# chipheater_01.net
KiCad netlist of a schematic drawn in EAGLE
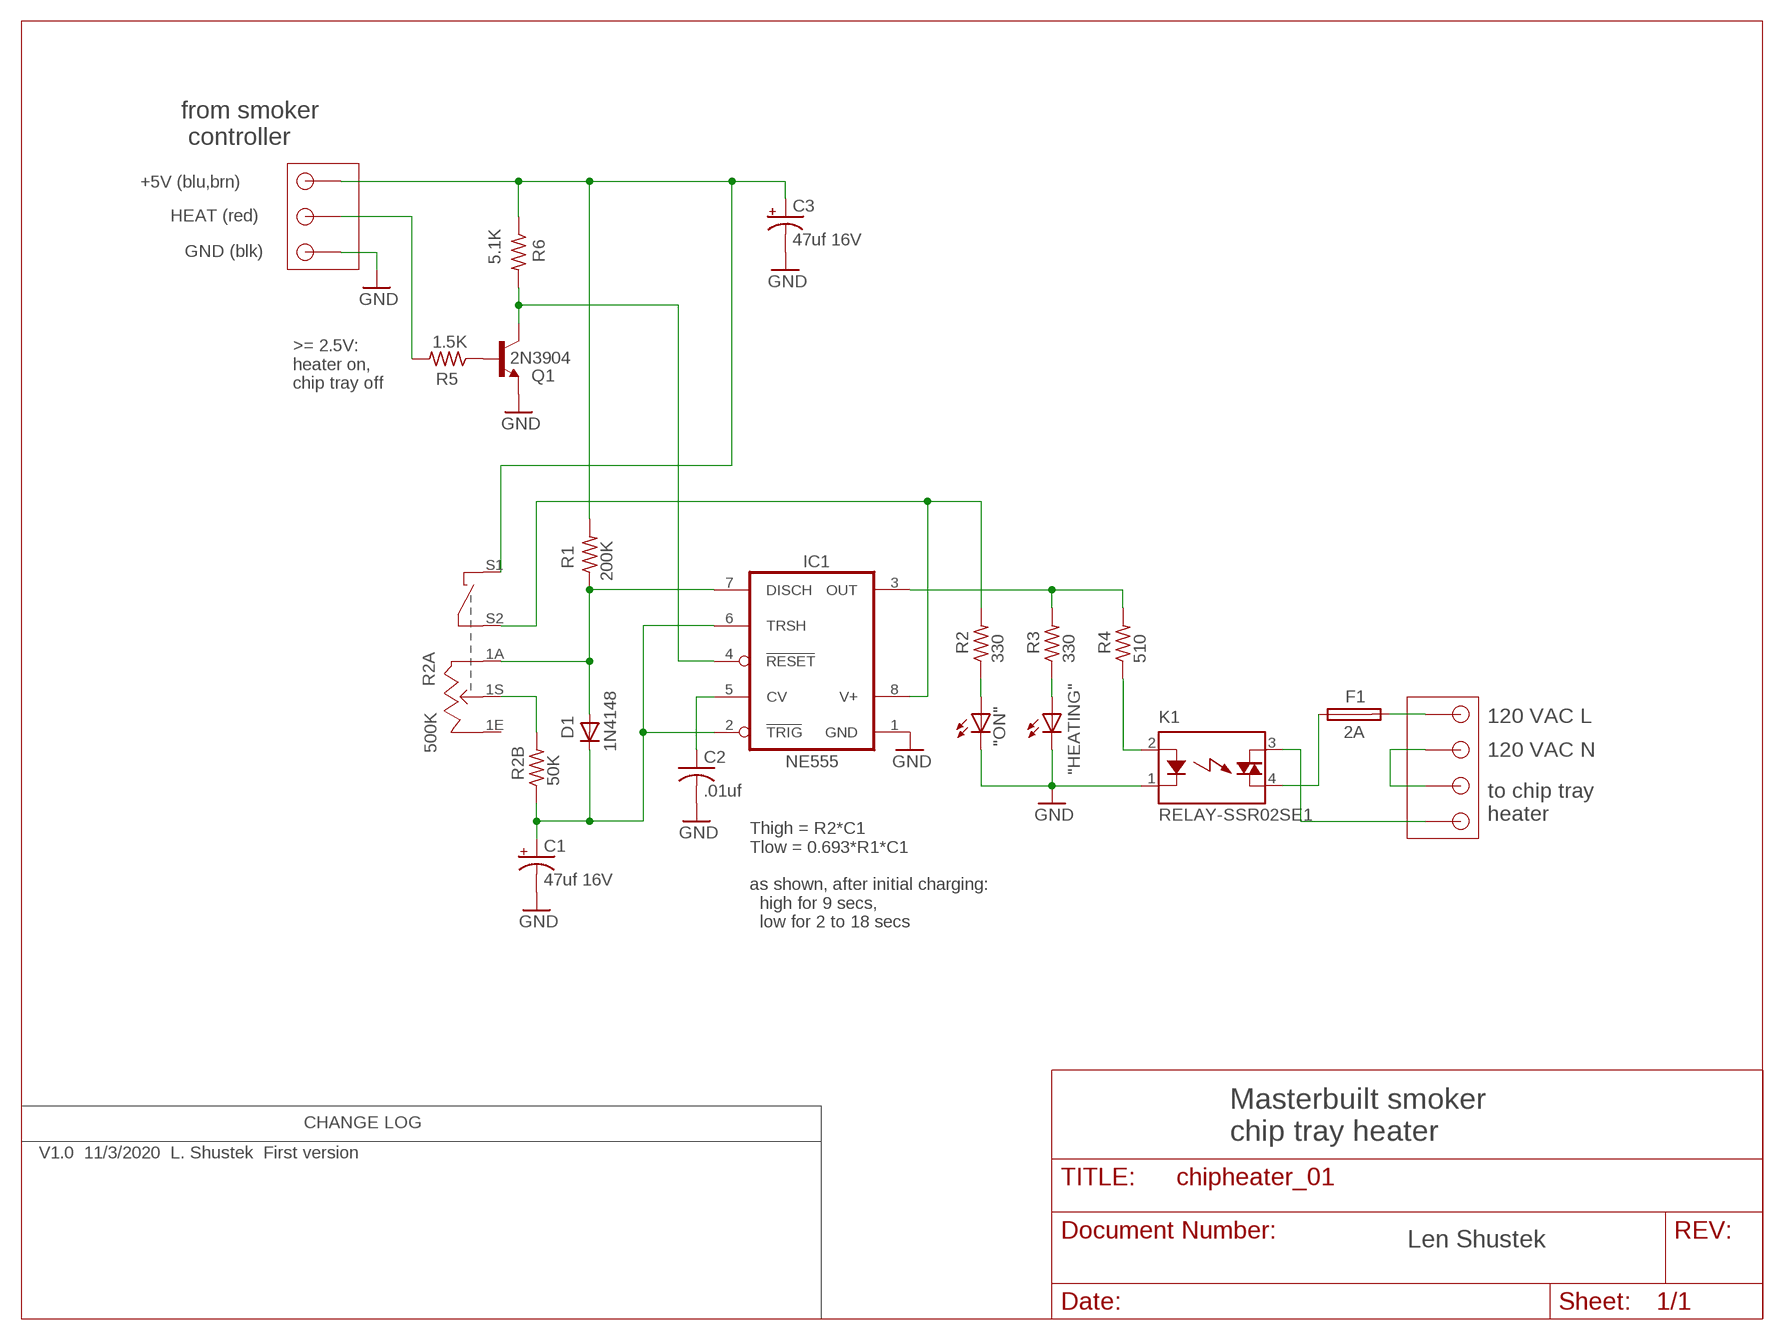
[diagram p0: schematic, sheet 1]

(export (version "E")
  (design (tool "Eeschema 10.0.6"))
  (components
    (comp (ref "\"HEATING\"")
      (value "LED5MM")
      (footprint "eagle-import:LED5MM")
      (libsource (lib "eagle-import") (part "LED5MM"))
    )
    (comp (ref "\"ON\"")
      (value "LED5MM")
      (footprint "eagle-import:LED5MM")
      (libsource (lib "eagle-import") (part "LED5MM"))
    )
    (comp (ref "C1")
      (value "47uf 16V")
      (footprint "eagle-import:E2,5-5")
      (libsource (lib "eagle-import") (part "CPOL-USE2.5-5"))
    )
    (comp (ref "C2")
      (value ".01uf")
      (footprint "eagle-import:C025-025X050")
      (libsource (lib "eagle-import") (part "C-US025-025X050"))
    )
    (comp (ref "C3")
      (value "47uf 16V")
      (footprint "eagle-import:E2,5-5")
      (libsource (lib "eagle-import") (part "CPOL-USE2.5-5"))
    )
    (comp (ref "D1")
      (value "1N4148")
      (footprint "eagle-import:DO-1N4148")
      (libsource (lib "eagle-import") (part "DIODEDO-1N4148"))
    )
    (comp (ref "F1")
      (value "2A")
      (footprint "eagle-import:SH22,5A")
      (libsource (lib "eagle-import") (part "FUSESH22,5A"))
    )
    (comp (ref "IC1")
      (value "NE555")
      (footprint "eagle-import:DIL08")
      (fields (field (name "MF") "MAXIM") (field (name "MPN") "ICM7555IPA+"))
      (libsource (lib "eagle-import") (part "ICM7555"))
    )
    (comp (ref "K1")
      (value "RELAY-SSR02SE1")
      (footprint "eagle-import:RELAY-SSR")
      (libsource (lib "eagle-import") (part "RELAY-SSR02SE1"))
    )
    (comp (ref "Q1")
      (value "2N3904")
      (footprint "eagle-import:TO92")
      (libsource (lib "eagle-import") (part "2N3904"))
    )
    (comp (ref "R1")
      (value "200K")
      (footprint "eagle-import:0204_7")
      (libsource (lib "eagle-import") (part "R-US_0204/7"))
    )
    (comp (ref "R2")
      (value "330")
      (footprint "eagle-import:0204_7")
      (libsource (lib "eagle-import") (part "R-US_0204/7"))
    )
    (comp (ref "R2A")
      (value "500K")
      (footprint "eagle-import:POT_W_SWITCH-UXCELL")
      (libsource (lib "eagle-import") (part "POT_W/SWITCHUXCELL"))
    )
    (comp (ref "R2B")
      (value "50K")
      (footprint "eagle-import:0204_7")
      (libsource (lib "eagle-import") (part "R-US_0204/7"))
    )
    (comp (ref "R3")
      (value "330")
      (footprint "eagle-import:0204_7")
      (libsource (lib "eagle-import") (part "R-US_0204/7"))
    )
    (comp (ref "R4")
      (value "510")
      (footprint "eagle-import:0204_7")
      (libsource (lib "eagle-import") (part "R-US_0204/7"))
    )
    (comp (ref "R5")
      (value "1.5K")
      (footprint "eagle-import:0204_7")
      (libsource (lib "eagle-import") (part "R-US_0204/7"))
    )
    (comp (ref "R6")
      (value "5.1K")
      (footprint "eagle-import:0204_7")
      (libsource (lib "eagle-import") (part "R-US_0204/7"))
    )
    (comp (ref "U$1")
      (value "CONNECTOR-4PIN")
      (footprint "eagle-import:CONNECTOR-4PIN-5MM_THIN")
      (libsource (lib "eagle-import") (part "CONNECTOR-4PIN"))
    )
    (comp (ref "U$2")
      (value "CONNECTOR-3PIN")
      (footprint "eagle-import:CONNECTOR-3PIN-5MM_THIN")
      (libsource (lib "eagle-import") (part "CONNECTOR-3PIN"))
    )
  )
  (nets
    (net (code "1") (name "GND") (class "Default")
      (node (ref "\"HEATING\"") (pin "K") (pinfunction "C_K") (pintype "passive"))
      (node (ref "\"ON\"") (pin "K") (pinfunction "C_K") (pintype "passive"))
      (node (ref "C1") (pin "-") (pinfunction "-_-") (pintype "passive"))
      (node (ref "C2") (pin "2") (pinfunction "2_2") (pintype "passive"))
      (node (ref "C3") (pin "-") (pinfunction "-_-") (pintype "passive"))
      (node (ref "IC1") (pin "1") (pinfunction "GND_1") (pintype "power_in"))
      (node (ref "K1") (pin "1") (pinfunction "K_1") (pintype "passive"))
      (node (ref "Q1") (pin "3") (pinfunction "E_3") (pintype "passive"))
      (node (ref "U$2") (pin "P$1") (pinfunction "P$1_P$1") (pintype "bidirectional"))
    )
    (net (code "2") (name "Net-(\"HEATING\"-PadA)") (class "Default")
      (node (ref "\"HEATING\"") (pin "A") (pinfunction "A_A") (pintype "passive"))
      (node (ref "R3") (pin "1") (pinfunction "1_1") (pintype "passive"))
    )
    (net (code "3") (name "Net-(\"ON\"-PadA)") (class "Default")
      (node (ref "\"ON\"") (pin "A") (pinfunction "A_A") (pintype "passive"))
      (node (ref "R2") (pin "1") (pinfunction "1_1") (pintype "passive"))
    )
    (net (code "4") (name "Net-(C3-Pad+)") (class "Default")
      (node (ref "C3") (pin "+") (pinfunction "+_+") (pintype "passive"))
      (node (ref "R1") (pin "2") (pinfunction "2_2") (pintype "passive"))
      (node (ref "R2A") (pin "S1") (pinfunction "S1_S1") (pintype "passive"))
      (node (ref "R6") (pin "1") (pinfunction "1_1") (pintype "passive"))
      (node (ref "U$2") (pin "P$3") (pinfunction "P$3_P$3") (pintype "bidirectional"))
    )
    (net (code "5") (name "Net-(F1-Pad2)") (class "Default")
      (node (ref "F1") (pin "2") (pinfunction "2_2") (pintype "passive"))
      (node (ref "U$1") (pin "P$1") (pinfunction "P$1_P$1") (pintype "bidirectional"))
    )
    (net (code "6") (name "Net-(IC1-CV)") (class "Default")
      (node (ref "C2") (pin "1") (pinfunction "1_1") (pintype "passive"))
      (node (ref "IC1") (pin "5") (pinfunction "CV_5") (pintype "passive"))
    )
    (net (code "7") (name "Net-(IC1-DISCH)") (class "Default")
      (node (ref "D1") (pin "A") (pinfunction "A_A") (pintype "passive"))
      (node (ref "IC1") (pin "7") (pinfunction "DISCH_7") (pintype "input"))
      (node (ref "R1") (pin "1") (pinfunction "1_1") (pintype "passive"))
      (node (ref "R2A") (pin "1A") (pinfunction "1A_1A") (pintype "passive"))
    )
    (net (code "8") (name "Net-(IC1-OUT)") (class "Default")
      (node (ref "IC1") (pin "3") (pinfunction "OUT_3") (pintype "output"))
      (node (ref "R3") (pin "2") (pinfunction "2_2") (pintype "passive"))
      (node (ref "R4") (pin "2") (pinfunction "2_2") (pintype "passive"))
    )
    (net (code "9") (name "Net-(IC1-RESET)") (class "Default")
      (node (ref "IC1") (pin "4") (pinfunction "RESET_4") (pintype "input"))
      (node (ref "Q1") (pin "1") (pinfunction "C_1") (pintype "passive"))
      (node (ref "R6") (pin "2") (pinfunction "2_2") (pintype "passive"))
    )
    (net (code "10") (name "Net-(IC1-TRIG)") (class "Default")
      (node (ref "C1") (pin "+") (pinfunction "+_+") (pintype "passive"))
      (node (ref "D1") (pin "C") (pinfunction "C_C") (pintype "passive"))
      (node (ref "IC1") (pin "2") (pinfunction "TRIG_2") (pintype "bidirectional"))
      (node (ref "IC1") (pin "6") (pinfunction "TRSH_6") (pintype "input"))
      (node (ref "R2B") (pin "1") (pinfunction "1_1") (pintype "passive"))
    )
    (net (code "11") (name "Net-(IC1-V+)") (class "Default")
      (node (ref "IC1") (pin "8") (pinfunction "V+_8") (pintype "power_in"))
      (node (ref "R2") (pin "2") (pinfunction "2_2") (pintype "passive"))
      (node (ref "R2A") (pin "S2") (pinfunction "S2_S2") (pintype "passive"))
    )
    (net (code "12") (name "Net-(K1-A)") (class "Default")
      (node (ref "K1") (pin "2") (pinfunction "A_2") (pintype "passive"))
      (node (ref "R4") (pin "1") (pinfunction "1_1") (pintype "passive"))
    )
    (net (code "13") (name "Net-(K1-DS1)") (class "Default")
      (node (ref "K1") (pin "3") (pinfunction "DS1_3") (pintype "passive"))
      (node (ref "U$1") (pin "P$4") (pinfunction "P$4_P$4") (pintype "bidirectional"))
    )
    (net (code "14") (name "Net-(K1-DS2)") (class "Default")
      (node (ref "F1") (pin "1") (pinfunction "1_1") (pintype "passive"))
      (node (ref "K1") (pin "4") (pinfunction "DS2_4") (pintype "passive"))
    )
    (net (code "15") (name "Net-(Q1-B)") (class "Default")
      (node (ref "Q1") (pin "2") (pinfunction "B_2") (pintype "passive"))
      (node (ref "R5") (pin "1") (pinfunction "1_1") (pintype "passive"))
    )
    (net (code "16") (name "Net-(R2A-Pad1S)") (class "Default")
      (node (ref "R2A") (pin "1S") (pinfunction "1S_1S") (pintype "passive"))
      (node (ref "R2B") (pin "2") (pinfunction "2_2") (pintype "passive"))
    )
    (net (code "17") (name "Net-(R5-Pad2)") (class "Default")
      (node (ref "R5") (pin "2") (pinfunction "2_2") (pintype "passive"))
      (node (ref "U$2") (pin "P$2") (pinfunction "P$2_P$2") (pintype "bidirectional"))
    )
    (net (code "18") (name "Net-(U$1-PadP$2)") (class "Default")
      (node (ref "U$1") (pin "P$2") (pinfunction "P$2_P$2") (pintype "bidirectional"))
      (node (ref "U$1") (pin "P$3") (pinfunction "P$3_P$3") (pintype "bidirectional"))
    )
    (net (code "19") (name "unconnected-(R2A-Pad1E)") (class "Default")
      (node (ref "R2A") (pin "1E") (pinfunction "1E_1E") (pintype "passive"))
    )
  )
)
